# KeyInput_MG.net
KiCad netlist of a schematic drawn in Altium Designer
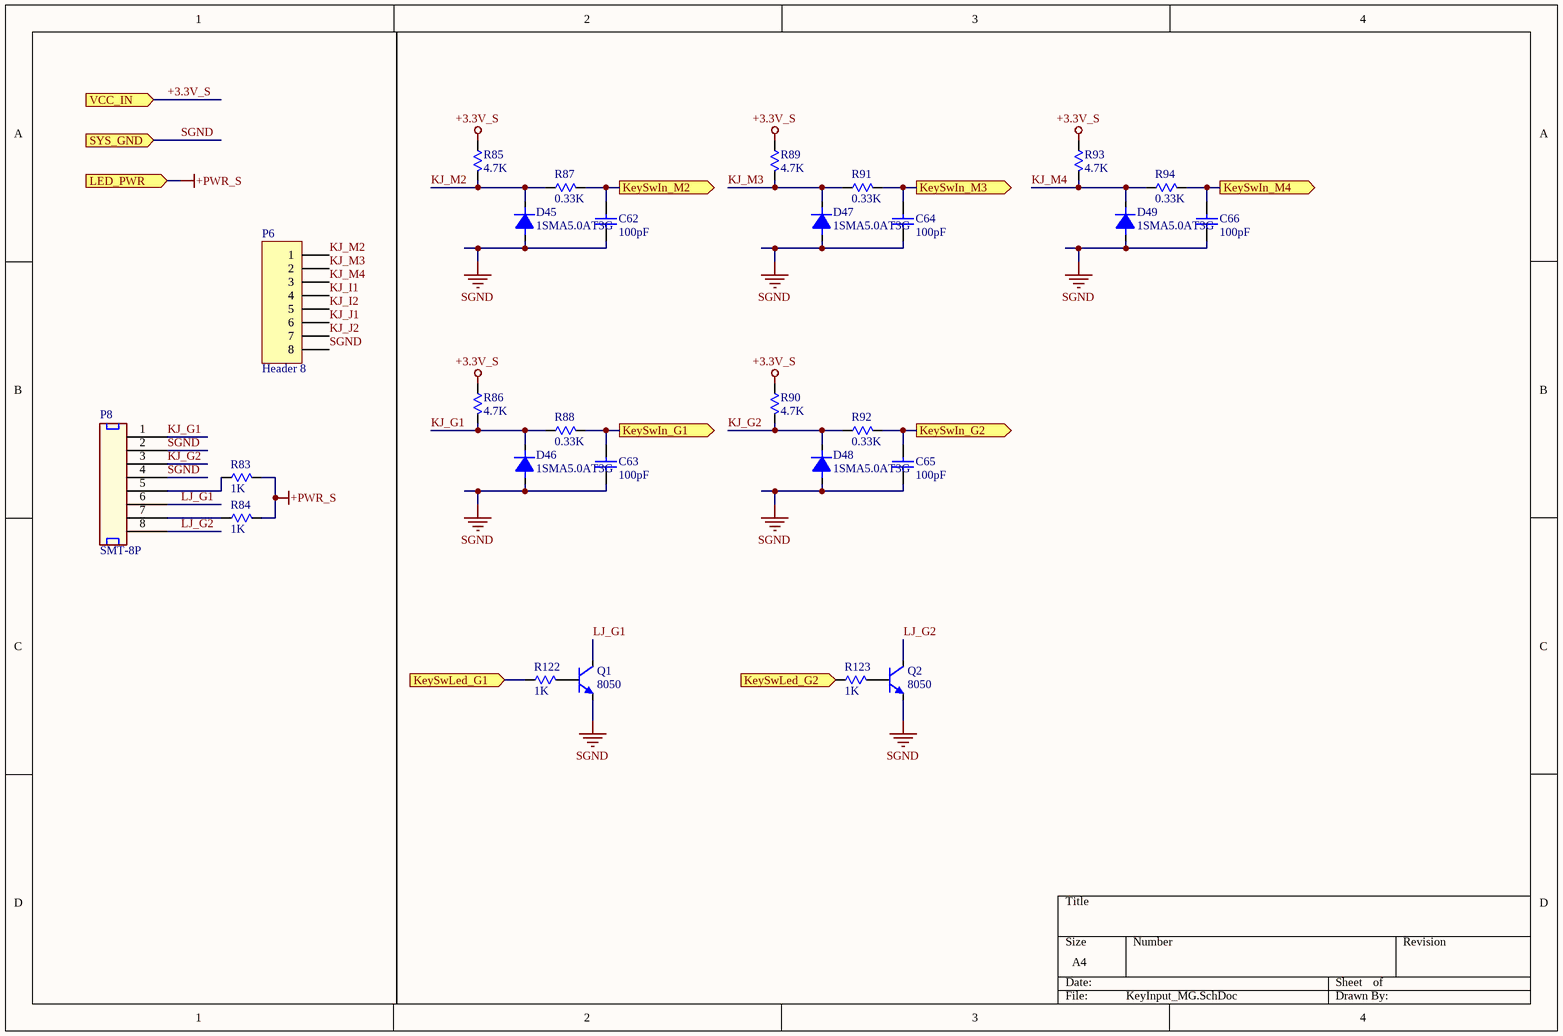
[diagram p0: KeyInput_MG.SchDoc]

(export (version "E")
  (design (tool "Eeschema 10.0.6"))
  (components
    (comp (ref "C62")
      (value "100pF")
      (footprint "C0805")
      (description "Capacitor")
      (fields (field (name "PUBLISHER") "Altium Limited"))
      (libsource (lib "Miscellaneous Devices") (part "Cap"))
    )
    (comp (ref "C63")
      (value "100pF")
      (footprint "C0805")
      (description "Capacitor")
      (fields (field (name "PUBLISHER") "Altium Limited"))
      (libsource (lib "Miscellaneous Devices") (part "Cap"))
    )
    (comp (ref "C64")
      (value "100pF")
      (footprint "C0805")
      (description "Capacitor")
      (fields (field (name "PUBLISHER") "Altium Limited"))
      (libsource (lib "Miscellaneous Devices") (part "Cap"))
    )
    (comp (ref "C65")
      (value "100pF")
      (footprint "C0805")
      (description "Capacitor")
      (fields (field (name "PUBLISHER") "Altium Limited"))
      (libsource (lib "Miscellaneous Devices") (part "Cap"))
    )
    (comp (ref "C66")
      (value "100pF")
      (footprint "C0805")
      (description "Capacitor")
      (fields (field (name "PUBLISHER") "Altium Limited"))
      (libsource (lib "Miscellaneous Devices") (part "Cap"))
    )
    (comp (ref "D45")
      (value "1SMA5.0AT3G")
      (footprint "SMA")
      (description "Diode")
      (libsource (lib "*") (part "DIODE1"))
    )
    (comp (ref "D46")
      (value "1SMA5.0AT3G")
      (footprint "SMA")
      (description "Diode")
      (libsource (lib "*") (part "DIODE1"))
    )
    (comp (ref "D47")
      (value "1SMA5.0AT3G")
      (footprint "SMA")
      (description "Diode")
      (libsource (lib "*") (part "DIODE1"))
    )
    (comp (ref "D48")
      (value "1SMA5.0AT3G")
      (footprint "SMA")
      (description "Diode")
      (libsource (lib "*") (part "DIODE1"))
    )
    (comp (ref "D49")
      (value "1SMA5.0AT3G")
      (footprint "SMA")
      (description "Diode")
      (libsource (lib "*") (part "DIODE1"))
    )
    (comp (ref "P6")
      (value "Header 8")
      (footprint "FFC/SM1.0-8")
      (description "Header, 8-Pin")
      (fields (field (name "PUBLISHER") "Altium Limited"))
      (libsource (lib "Miscellaneous Connectors") (part "Header 8"))
    )
    (comp (ref "P8")
      (value "SMT-8P")
      (footprint "1MM25_8PIN_SMT_R90")
      (libsource (lib "Connector Class") (part "SMT-8P"))
    )
    (comp (ref "Q1")
      (value "8050")
      (footprint "SOT-23")
      (description "NPN General Purpose Amplifier")
      (fields (field (name "PUBLISHER") "Altium Limited"))
      (libsource (lib "Bdmc4810") (part "NPN"))
    )
    (comp (ref "Q2")
      (value "8050")
      (footprint "SOT-23")
      (description "NPN General Purpose Amplifier")
      (fields (field (name "PUBLISHER") "Altium Limited"))
      (libsource (lib "Bdmc4810") (part "NPN"))
    )
    (comp (ref "R83")
      (value "1K")
      (footprint "R0805")
      (description "Resistor")
      (fields (field (name "PUBLISHER") "Altium Limited"))
      (libsource (lib "Passive Components Class") (part "RES"))
    )
    (comp (ref "R84")
      (value "1K")
      (footprint "R0805")
      (description "Resistor")
      (fields (field (name "PUBLISHER") "Altium Limited"))
      (libsource (lib "Passive Components Class") (part "RES"))
    )
    (comp (ref "R85")
      (value "4.7K")
      (footprint "R0805")
      (description "Resistor")
      (fields (field (name "PUBLISHER") "Altium Limited"))
      (libsource (lib "Passive Components Class") (part "RES"))
    )
    (comp (ref "R86")
      (value "4.7K")
      (footprint "R0805")
      (description "Resistor")
      (fields (field (name "PUBLISHER") "Altium Limited"))
      (libsource (lib "Passive Components Class") (part "RES"))
    )
    (comp (ref "R87")
      (value "0.33K")
      (footprint "R0805")
      (description "Resistor")
      (fields (field (name "PUBLISHER") "Altium Limited"))
      (libsource (lib "Passive Components Class") (part "RES"))
    )
    (comp (ref "R88")
      (value "0.33K")
      (footprint "R0805")
      (description "Resistor")
      (fields (field (name "PUBLISHER") "Altium Limited"))
      (libsource (lib "Passive Components Class") (part "RES"))
    )
    (comp (ref "R89")
      (value "4.7K")
      (footprint "R0805")
      (description "Resistor")
      (fields (field (name "PUBLISHER") "Altium Limited"))
      (libsource (lib "Passive Components Class") (part "RES"))
    )
    (comp (ref "R90")
      (value "4.7K")
      (footprint "R0805")
      (description "Resistor")
      (fields (field (name "PUBLISHER") "Altium Limited"))
      (libsource (lib "Passive Components Class") (part "RES"))
    )
    (comp (ref "R91")
      (value "0.33K")
      (footprint "R0805")
      (description "Resistor")
      (fields (field (name "PUBLISHER") "Altium Limited"))
      (libsource (lib "Passive Components Class") (part "RES"))
    )
    (comp (ref "R92")
      (value "0.33K")
      (footprint "R0805")
      (description "Resistor")
      (fields (field (name "PUBLISHER") "Altium Limited"))
      (libsource (lib "Passive Components Class") (part "RES"))
    )
    (comp (ref "R93")
      (value "4.7K")
      (footprint "R0805")
      (description "Resistor")
      (fields (field (name "PUBLISHER") "Altium Limited"))
      (libsource (lib "Passive Components Class") (part "RES"))
    )
    (comp (ref "R94")
      (value "0.33K")
      (footprint "R0805")
      (description "Resistor")
      (fields (field (name "PUBLISHER") "Altium Limited"))
      (libsource (lib "Passive Components Class") (part "RES"))
    )
    (comp (ref "R122")
      (value "1K")
      (footprint "R0805")
      (description "Resistor")
      (fields (field (name "PUBLISHER") "Altium Limited"))
      (libsource (lib "Passive Components Class") (part "RES"))
    )
    (comp (ref "R123")
      (value "1K")
      (footprint "R0805")
      (description "Resistor")
      (fields (field (name "PUBLISHER") "Altium Limited"))
      (libsource (lib "Passive Components Class") (part "RES"))
    )
  )
  (nets
    (net (code "1") (name "+3.3V_S") (class "Default")
      (node (ref "R85") (pin "2") (pinfunction "2_2") (pintype "passive"))
      (node (ref "R86") (pin "2") (pinfunction "2_2") (pintype "passive"))
      (node (ref "R89") (pin "2") (pinfunction "2_2") (pintype "passive"))
      (node (ref "R90") (pin "2") (pinfunction "2_2") (pintype "passive"))
      (node (ref "R93") (pin "2") (pinfunction "2_2") (pintype "passive"))
    )
    (net (code "2") (name "+PWR_S") (class "Default")
      (node (ref "R83") (pin "1") (pinfunction "1_1") (pintype "passive"))
      (node (ref "R84") (pin "1") (pinfunction "1_1") (pintype "passive"))
    )
    (net (code "3") (name "/KJ_G1") (class "Default")
      (node (ref "D46") (pin "2") (pinfunction "K_2") (pintype "passive"))
      (node (ref "P8") (pin "1") (pinfunction "1_1") (pintype "passive"))
      (node (ref "R86") (pin "1") (pinfunction "1_1") (pintype "passive"))
      (node (ref "R88") (pin "2") (pinfunction "2_2") (pintype "passive"))
    )
    (net (code "4") (name "/KJ_G2") (class "Default")
      (node (ref "D48") (pin "2") (pinfunction "K_2") (pintype "passive"))
      (node (ref "P8") (pin "3") (pinfunction "3_3") (pintype "passive"))
      (node (ref "R90") (pin "1") (pinfunction "1_1") (pintype "passive"))
      (node (ref "R92") (pin "2") (pinfunction "2_2") (pintype "passive"))
    )
    (net (code "5") (name "/KJ_I1") (class "Default")
      (node (ref "P6") (pin "4") (pinfunction "4_4") (pintype "passive"))
    )
    (net (code "6") (name "/KJ_I2") (class "Default")
      (node (ref "P6") (pin "5") (pinfunction "5_5") (pintype "passive"))
    )
    (net (code "7") (name "/KJ_J1") (class "Default")
      (node (ref "P6") (pin "6") (pinfunction "6_6") (pintype "passive"))
    )
    (net (code "8") (name "/KJ_J2") (class "Default")
      (node (ref "P6") (pin "7") (pinfunction "7_7") (pintype "passive"))
    )
    (net (code "9") (name "/KJ_M2") (class "Default")
      (node (ref "D45") (pin "2") (pinfunction "K_2") (pintype "passive"))
      (node (ref "P6") (pin "1") (pinfunction "1_1") (pintype "passive"))
      (node (ref "R85") (pin "1") (pinfunction "1_1") (pintype "passive"))
      (node (ref "R87") (pin "2") (pinfunction "2_2") (pintype "passive"))
    )
    (net (code "10") (name "/KJ_M3") (class "Default")
      (node (ref "D47") (pin "2") (pinfunction "K_2") (pintype "passive"))
      (node (ref "P6") (pin "2") (pinfunction "2_2") (pintype "passive"))
      (node (ref "R89") (pin "1") (pinfunction "1_1") (pintype "passive"))
      (node (ref "R91") (pin "2") (pinfunction "2_2") (pintype "passive"))
    )
    (net (code "11") (name "/KJ_M4") (class "Default")
      (node (ref "D49") (pin "2") (pinfunction "K_2") (pintype "passive"))
      (node (ref "P6") (pin "3") (pinfunction "3_3") (pintype "passive"))
      (node (ref "R93") (pin "1") (pinfunction "1_1") (pintype "passive"))
      (node (ref "R94") (pin "2") (pinfunction "2_2") (pintype "passive"))
    )
    (net (code "12") (name "/KeySwIn_G1") (class "Default")
      (node (ref "C63") (pin "1") (pinfunction "1_1") (pintype "passive"))
      (node (ref "R88") (pin "1") (pinfunction "1_1") (pintype "passive"))
    )
    (net (code "13") (name "/KeySwIn_G2") (class "Default")
      (node (ref "C65") (pin "1") (pinfunction "1_1") (pintype "passive"))
      (node (ref "R92") (pin "1") (pinfunction "1_1") (pintype "passive"))
    )
    (net (code "14") (name "/KeySwIn_M2") (class "Default")
      (node (ref "C62") (pin "1") (pinfunction "1_1") (pintype "passive"))
      (node (ref "R87") (pin "1") (pinfunction "1_1") (pintype "passive"))
    )
    (net (code "15") (name "/KeySwIn_M3") (class "Default")
      (node (ref "C64") (pin "1") (pinfunction "1_1") (pintype "passive"))
      (node (ref "R91") (pin "1") (pinfunction "1_1") (pintype "passive"))
    )
    (net (code "16") (name "/KeySwIn_M4") (class "Default")
      (node (ref "C66") (pin "1") (pinfunction "1_1") (pintype "passive"))
      (node (ref "R94") (pin "1") (pinfunction "1_1") (pintype "passive"))
    )
    (net (code "17") (name "/KeySwLed_G1") (class "Default")
      (node (ref "R122") (pin "2") (pinfunction "2_2") (pintype "passive"))
    )
    (net (code "18") (name "/KeySwLed_G2") (class "Default")
      (node (ref "R123") (pin "2") (pinfunction "2_2") (pintype "passive"))
    )
    (net (code "19") (name "/LJ_G1") (class "Default")
      (node (ref "P8") (pin "6") (pinfunction "6_6") (pintype "passive"))
      (node (ref "Q1") (pin "3") (pinfunction "C_3") (pintype "passive"))
    )
    (net (code "20") (name "/LJ_G2") (class "Default")
      (node (ref "P8") (pin "8") (pinfunction "8_8") (pintype "passive"))
      (node (ref "Q2") (pin "3") (pinfunction "C_3") (pintype "passive"))
    )
    (net (code "21") (name "Net-(P8-Pad5)") (class "Default")
      (node (ref "P8") (pin "5") (pinfunction "5_5") (pintype "passive"))
      (node (ref "R83") (pin "2") (pinfunction "2_2") (pintype "passive"))
    )
    (net (code "22") (name "Net-(P8-Pad7)") (class "Default")
      (node (ref "P8") (pin "7") (pinfunction "7_7") (pintype "passive"))
      (node (ref "R84") (pin "2") (pinfunction "2_2") (pintype "passive"))
    )
    (net (code "23") (name "Net-(Q1-B)") (class "Default")
      (node (ref "Q1") (pin "1") (pinfunction "B_1") (pintype "passive"))
      (node (ref "R122") (pin "1") (pinfunction "1_1") (pintype "passive"))
    )
    (net (code "24") (name "Net-(Q2-B)") (class "Default")
      (node (ref "Q2") (pin "1") (pinfunction "B_1") (pintype "passive"))
      (node (ref "R123") (pin "1") (pinfunction "1_1") (pintype "passive"))
    )
    (net (code "25") (name "SGND") (class "Default")
      (node (ref "C62") (pin "2") (pinfunction "2_2") (pintype "passive"))
      (node (ref "C63") (pin "2") (pinfunction "2_2") (pintype "passive"))
      (node (ref "C64") (pin "2") (pinfunction "2_2") (pintype "passive"))
      (node (ref "C65") (pin "2") (pinfunction "2_2") (pintype "passive"))
      (node (ref "C66") (pin "2") (pinfunction "2_2") (pintype "passive"))
      (node (ref "D45") (pin "1") (pinfunction "A_1") (pintype "passive"))
      (node (ref "D46") (pin "1") (pinfunction "A_1") (pintype "passive"))
      (node (ref "D47") (pin "1") (pinfunction "A_1") (pintype "passive"))
      (node (ref "D48") (pin "1") (pinfunction "A_1") (pintype "passive"))
      (node (ref "D49") (pin "1") (pinfunction "A_1") (pintype "passive"))
      (node (ref "P6") (pin "8") (pinfunction "8_8") (pintype "passive"))
      (node (ref "P8") (pin "2") (pinfunction "2_2") (pintype "passive"))
      (node (ref "P8") (pin "4") (pinfunction "4_4") (pintype "passive"))
      (node (ref "Q1") (pin "2") (pinfunction "E_2") (pintype "passive"))
      (node (ref "Q2") (pin "2") (pinfunction "E_2") (pintype "passive"))
    )
  )
)
